# sigma_delta_v1_0.net
KiCad netlist of a schematic drawn in EAGLE
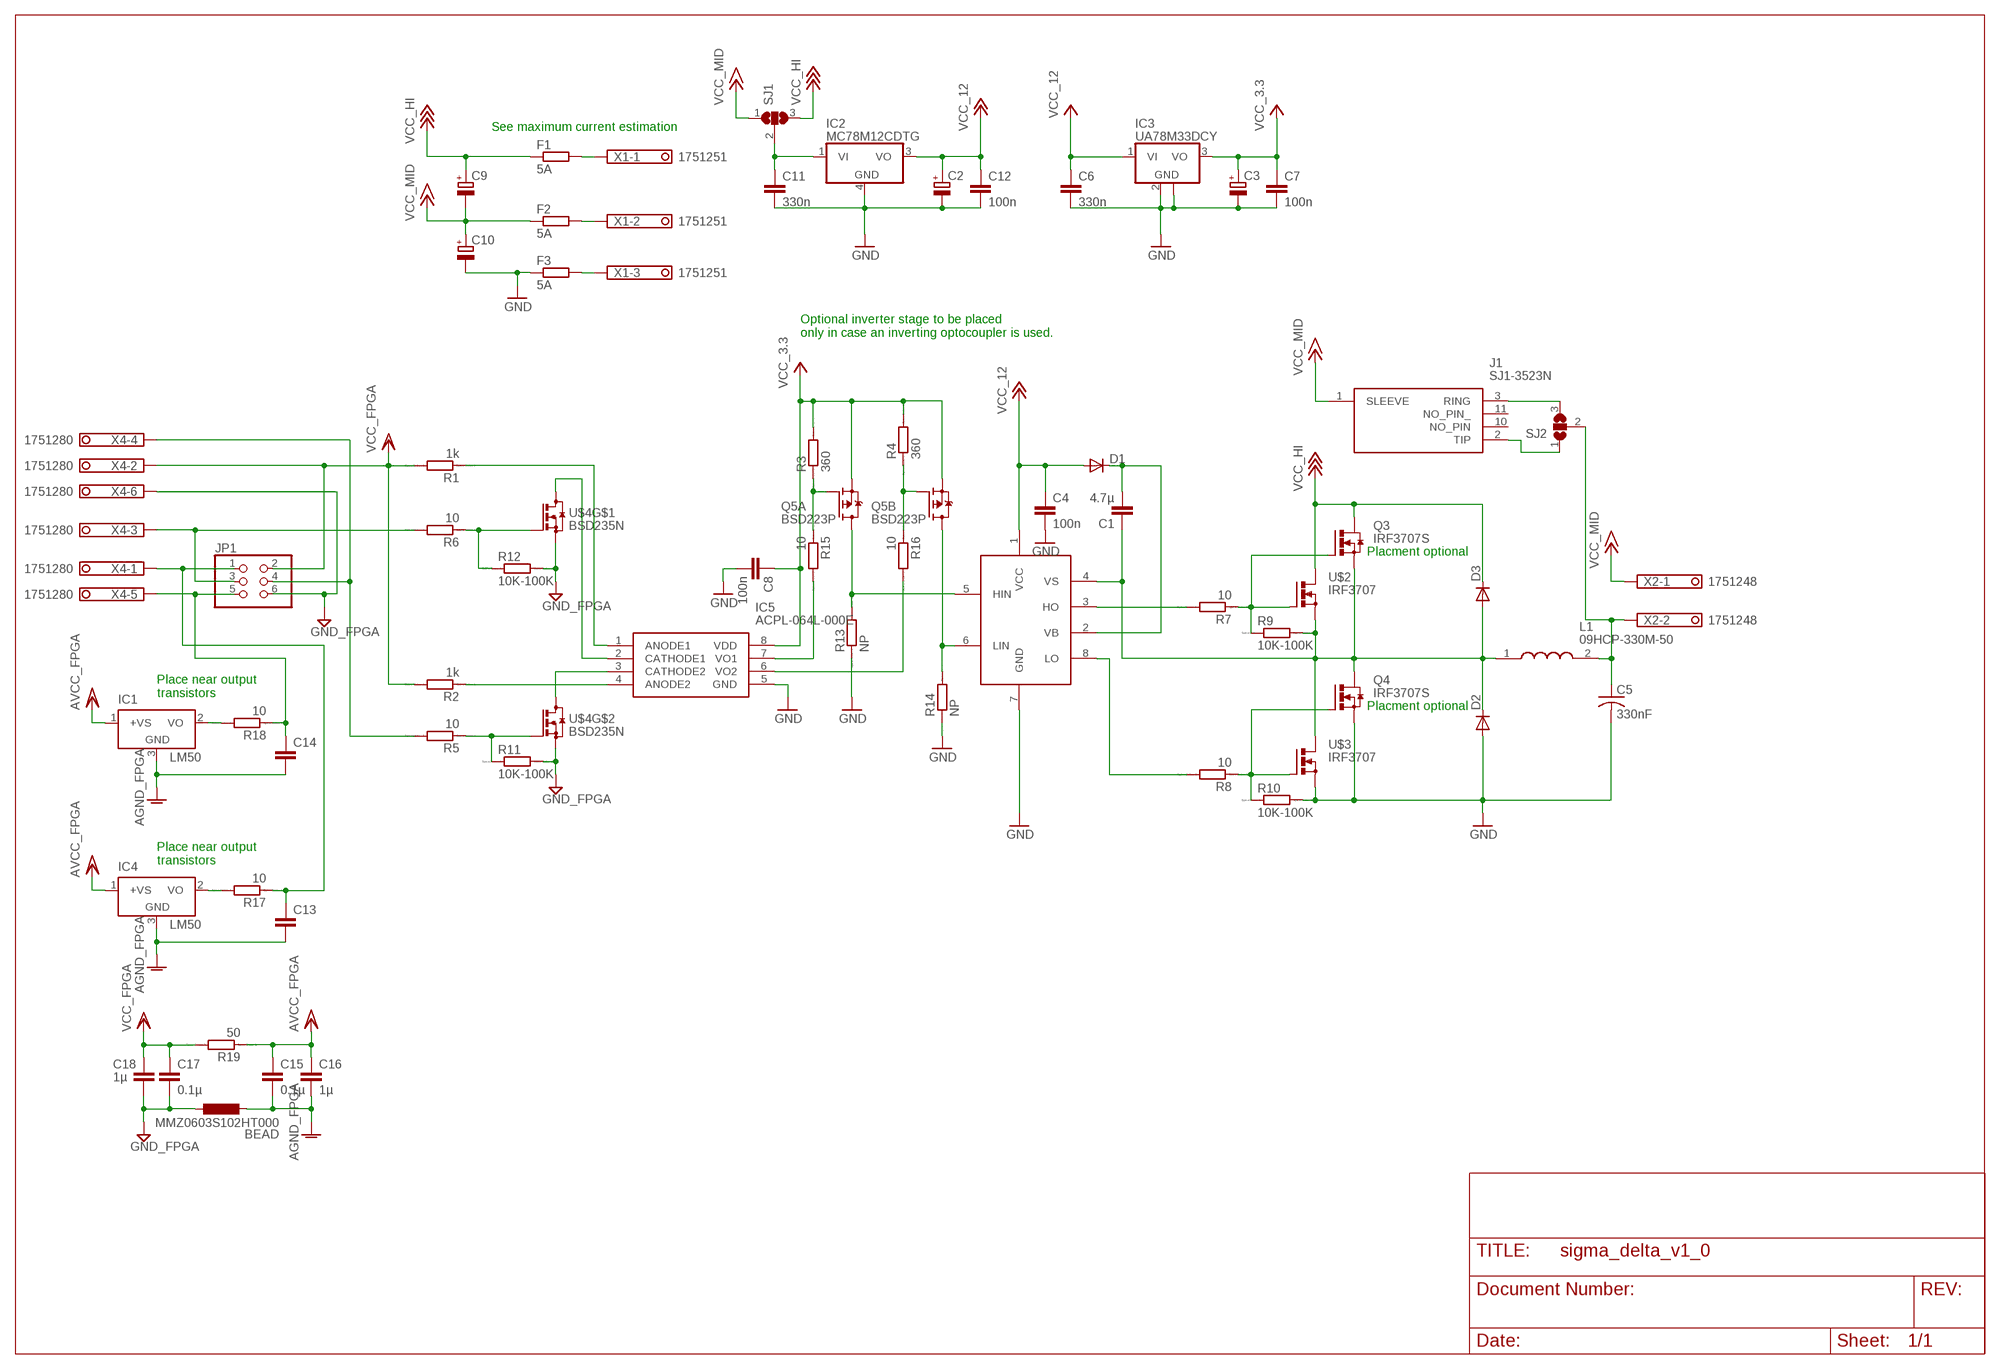
[diagram p0: schematic, sheet 1]

(export (version "E")
  (design (tool "Eeschema 10.0.6"))
  (components
    (comp (ref "BEAD")
      (value "MMZ0603S102HT000")
      (footprint "eagle-import:L2012C")
      (libsource (lib "eagle-import") (part "L-EUL2012C"))
    )
    (comp (ref "C1")
      (value "4.7µ")
      (footprint "eagle-import:C0805K")
      (libsource (lib "eagle-import") (part "C-EUC0805K"))
    )
    (comp (ref "C2")
      (value "CPOL-EUUD-6,3X7,7")
      (footprint "eagle-import:UD-6,3X7,7_NICHICON")
      (libsource (lib "eagle-import") (part "CPOL-EUUD-6,3X7,7"))
    )
    (comp (ref "C3")
      (value "CPOL-EUUD-6,3X7,7")
      (footprint "eagle-import:UD-6,3X7,7_NICHICON")
      (libsource (lib "eagle-import") (part "CPOL-EUUD-6,3X7,7"))
    )
    (comp (ref "C4")
      (value "100n")
      (footprint "eagle-import:C0805")
      (libsource (lib "eagle-import") (part "C-EUC0805"))
    )
    (comp (ref "C5")
      (value "330nF")
      (footprint "eagle-import:C2220K")
      (libsource (lib "eagle-import") (part "C-USC2220K"))
    )
    (comp (ref "C6")
      (value "330n")
      (footprint "eagle-import:C0603")
      (libsource (lib "eagle-import") (part "C-EUC0603"))
    )
    (comp (ref "C7")
      (value "100n")
      (footprint "eagle-import:C0603")
      (libsource (lib "eagle-import") (part "C-EUC0603"))
    )
    (comp (ref "C8")
      (value "100n")
      (footprint "eagle-import:C0603")
      (libsource (lib "eagle-import") (part "C-EUC0603"))
    )
    (comp (ref "C9")
      (value "CPOL-EUUD-10X10")
      (footprint "eagle-import:UD-10X10_NICHICON")
      (libsource (lib "eagle-import") (part "CPOL-EUUD-10X10"))
    )
    (comp (ref "C10")
      (value "CPOL-EUUD-10X10")
      (footprint "eagle-import:UD-10X10_NICHICON")
      (libsource (lib "eagle-import") (part "CPOL-EUUD-10X10"))
    )
    (comp (ref "C11")
      (value "330n")
      (footprint "eagle-import:C0603")
      (libsource (lib "eagle-import") (part "C-EUC0603"))
    )
    (comp (ref "C12")
      (value "100n")
      (footprint "eagle-import:C0603")
      (libsource (lib "eagle-import") (part "C-EUC0603"))
    )
    (comp (ref "C13")
      (value "C-EUC0603")
      (footprint "eagle-import:C0603")
      (libsource (lib "eagle-import") (part "C-EUC0603"))
    )
    (comp (ref "C14")
      (value "C-EUC0603")
      (footprint "eagle-import:C0603")
      (libsource (lib "eagle-import") (part "C-EUC0603"))
    )
    (comp (ref "C15")
      (value "0.1µ")
      (footprint "eagle-import:C0603")
      (libsource (lib "eagle-import") (part "C-EUC0603"))
    )
    (comp (ref "C16")
      (value "1µ")
      (footprint "eagle-import:C0603")
      (libsource (lib "eagle-import") (part "C-EUC0603"))
    )
    (comp (ref "C17")
      (value "0.1µ")
      (footprint "eagle-import:C0603")
      (libsource (lib "eagle-import") (part "C-EUC0603"))
    )
    (comp (ref "C18")
      (value "1µ")
      (footprint "eagle-import:C0603")
      (libsource (lib "eagle-import") (part "C-EUC0603"))
    )
    (comp (ref "D1")
      (value "DIODE-DO214AC")
      (footprint "eagle-import:DO214AC")
      (libsource (lib "eagle-import") (part "DIODE-DO214AC"))
    )
    (comp (ref "D2")
      (value "DIODE-DO214AC")
      (footprint "eagle-import:DO214AC")
      (libsource (lib "eagle-import") (part "DIODE-DO214AC"))
    )
    (comp (ref "D3")
      (value "DIODE-DO214AC")
      (footprint "eagle-import:DO214AC")
      (libsource (lib "eagle-import") (part "DIODE-DO214AC"))
    )
    (comp (ref "F1")
      (value "5A")
      (footprint "eagle-import:M1206")
      (libsource (lib "eagle-import") (part "R-EU_M1206"))
    )
    (comp (ref "F2")
      (value "5A")
      (footprint "eagle-import:M1206")
      (libsource (lib "eagle-import") (part "R-EU_M1206"))
    )
    (comp (ref "F3")
      (value "5A")
      (footprint "eagle-import:M1206")
      (libsource (lib "eagle-import") (part "R-EU_M1206"))
    )
    (comp (ref "IC1")
      (value "LM50")
      (footprint "eagle-import:SOT23")
      (libsource (lib "eagle-import") (part "LM50"))
    )
    (comp (ref "IC2")
      (value "MC78M12CDTG")
      (footprint "eagle-import:DPACK_3")
      (libsource (lib "eagle-import") (part "MC78M12CDTG"))
    )
    (comp (ref "IC3")
      (value "UA78M33DCY")
      (footprint "eagle-import:SOT223")
      (libsource (lib "eagle-import") (part "UA78MDCY33"))
    )
    (comp (ref "IC4")
      (value "LM50")
      (footprint "eagle-import:SOT23")
      (libsource (lib "eagle-import") (part "LM50"))
    )
    (comp (ref "IC5")
      (value "ACPL-064L-000E")
      (footprint "eagle-import:SOIC127P599X330-8N")
      (fields (field (name "MOUSER_PART_NUMBER") "630-ACPL-064L-000E"))
      (libsource (lib "eagle-import") (part "ACPL-064L-000E"))
    )
    (comp (ref "J1")
      (value "SJ1-3523N")
      (footprint "eagle-import:SJ13523N")
      (fields (field (name "MOUSER_PART_NUMBER") "490-SJ1-3523N"))
      (libsource (lib "eagle-import") (part "SJ1-3523N"))
    )
    (comp (ref "JP1")
      (value "PINHD-2X3_2.54")
      (footprint "eagle-import:2X03")
      (libsource (lib "eagle-import") (part "PINHD-2X3_2.54"))
    )
    (comp (ref "L1")
      (value "09HCP-330M-50")
      (footprint "eagle-import:09HCP330M50")
      (fields (field (name "MOUSER_PART_NUMBER") "434-09HCP-330M"))
      (libsource (lib "eagle-import") (part "09HCP-330M-50"))
    )
    (comp (ref "Q3")
      (value "IRF3707S")
      (footprint "eagle-import:D2PACK")
      (libsource (lib "eagle-import") (part "IRF3704S"))
    )
    (comp (ref "Q4")
      (value "IRF3707S")
      (footprint "eagle-import:D2PACK")
      (libsource (lib "eagle-import") (part "IRF3704S"))
    )
    (comp (ref "Q5")
      (value "BSD223P")
      (footprint "eagle-import:SOT363_INFINEON")
      (libsource (lib "eagle-import") (part "BSD223P"))
    )
    (comp (ref "R1")
      (value "1k")
      (footprint "eagle-import:R0603")
      (libsource (lib "eagle-import") (part "RR0603"))
    )
    (comp (ref "R2")
      (value "1k")
      (footprint "eagle-import:R0603")
      (libsource (lib "eagle-import") (part "RR0603"))
    )
    (comp (ref "R3")
      (value "360")
      (footprint "eagle-import:R0603")
      (libsource (lib "eagle-import") (part "RR0603"))
    )
    (comp (ref "R4")
      (value "360")
      (footprint "eagle-import:R0603")
      (libsource (lib "eagle-import") (part "RR0603"))
    )
    (comp (ref "R5")
      (value "10")
      (footprint "eagle-import:R0603")
      (libsource (lib "eagle-import") (part "RR0603"))
    )
    (comp (ref "R6")
      (value "10")
      (footprint "eagle-import:R0603")
      (libsource (lib "eagle-import") (part "RR0603"))
    )
    (comp (ref "R7")
      (value "10")
      (footprint "eagle-import:R0603")
      (libsource (lib "eagle-import") (part "RR0603"))
    )
    (comp (ref "R8")
      (value "10")
      (footprint "eagle-import:R0603")
      (libsource (lib "eagle-import") (part "RR0603"))
    )
    (comp (ref "R9")
      (value "10K-100K")
      (footprint "eagle-import:R0603")
      (libsource (lib "eagle-import") (part "RR0603"))
    )
    (comp (ref "R10")
      (value "10K-100K")
      (footprint "eagle-import:R0603")
      (libsource (lib "eagle-import") (part "RR0603"))
    )
    (comp (ref "R11")
      (value "10K-100K")
      (footprint "eagle-import:R0603")
      (libsource (lib "eagle-import") (part "RR0603"))
    )
    (comp (ref "R12")
      (value "10K-100K")
      (footprint "eagle-import:R0603")
      (libsource (lib "eagle-import") (part "RR0603"))
    )
    (comp (ref "R13")
      (value "NP")
      (footprint "eagle-import:R0603")
      (libsource (lib "eagle-import") (part "RR0603"))
    )
    (comp (ref "R14")
      (value "NP")
      (footprint "eagle-import:R0603")
      (libsource (lib "eagle-import") (part "RR0603"))
    )
    (comp (ref "R15")
      (value "10")
      (footprint "eagle-import:R0603")
      (libsource (lib "eagle-import") (part "RR0603"))
    )
    (comp (ref "R16")
      (value "10")
      (footprint "eagle-import:R0603")
      (libsource (lib "eagle-import") (part "RR0603"))
    )
    (comp (ref "R17")
      (value "10")
      (footprint "eagle-import:R0603")
      (libsource (lib "eagle-import") (part "RR0603"))
    )
    (comp (ref "R18")
      (value "10")
      (footprint "eagle-import:R0603")
      (libsource (lib "eagle-import") (part "RR0603"))
    )
    (comp (ref "R19")
      (value "50")
      (footprint "eagle-import:R0603")
      (libsource (lib "eagle-import") (part "RR0603"))
    )
    (comp (ref "SJ1")
      (value "SJ2W")
      (footprint "eagle-import:SJ_2")
      (libsource (lib "eagle-import") (part "SJ2W"))
    )
    (comp (ref "SJ2")
      (value "SJ2WW")
      (footprint "eagle-import:SJ_2W")
      (libsource (lib "eagle-import") (part "SJ2WW"))
    )
    (comp (ref "U$1")
      (value "IR2011")
      (footprint "eagle-import:SO08")
      (libsource (lib "eagle-import") (part "IR2011"))
    )
    (comp (ref "U$2")
      (value "IRF3707")
      (footprint "eagle-import:TO220BV")
      (libsource (lib "eagle-import") (part "BUZ11BV"))
    )
    (comp (ref "U$3")
      (value "IRF3707")
      (footprint "eagle-import:TO220BV")
      (libsource (lib "eagle-import") (part "BUZ11BV"))
    )
    (comp (ref "U$4")
      (value "BSD235N")
      (footprint "eagle-import:SOT65P210X100-6N")
      (libsource (lib "eagle-import") (part "BSD235N"))
    )
    (comp (ref "X1")
      (value "1751251")
      (footprint "eagle-import:1751251")
      (libsource (lib "eagle-import") (part "1751251"))
    )
    (comp (ref "X2")
      (value "1751248")
      (footprint "eagle-import:1751248")
      (libsource (lib "eagle-import") (part "1751248"))
    )
    (comp (ref "X4")
      (value "1751280")
      (footprint "eagle-import:1751280")
      (libsource (lib "eagle-import") (part "1751280"))
    )
  )
  (nets
    (net (code "1") (name "AGND_FPGA") (class "Default")
      (node (ref "BEAD") (pin "2") (pinfunction "2_2") (pintype "passive"))
      (node (ref "C13") (pin "2") (pinfunction "2_2") (pintype "passive"))
      (node (ref "C14") (pin "2") (pinfunction "2_2") (pintype "passive"))
      (node (ref "C15") (pin "2") (pinfunction "2_2") (pintype "passive"))
      (node (ref "C16") (pin "2") (pinfunction "2_2") (pintype "passive"))
      (node (ref "IC1") (pin "3") (pinfunction "GND_3") (pintype "power_in"))
      (node (ref "IC4") (pin "3") (pinfunction "GND_3") (pintype "power_in"))
    )
    (net (code "2") (name "AVCC_FPGA") (class "Default")
      (node (ref "C15") (pin "1") (pinfunction "1_1") (pintype "passive"))
      (node (ref "C16") (pin "1") (pinfunction "1_1") (pintype "passive"))
      (node (ref "IC1") (pin "1") (pinfunction "+VS_1") (pintype "input"))
      (node (ref "IC4") (pin "1") (pinfunction "+VS_1") (pintype "input"))
      (node (ref "R19") (pin "1") (pinfunction "1_1") (pintype "passive"))
    )
    (net (code "3") (name "GND") (class "Default")
      (node (ref "C10") (pin "-") (pinfunction "-_-") (pintype "passive"))
      (node (ref "C11") (pin "2") (pinfunction "2_2") (pintype "passive"))
      (node (ref "C12") (pin "2") (pinfunction "2_2") (pintype "passive"))
      (node (ref "C2") (pin "-") (pinfunction "-_-") (pintype "passive"))
      (node (ref "C3") (pin "-") (pinfunction "-_-") (pintype "passive"))
      (node (ref "C4") (pin "2") (pinfunction "2_2") (pintype "passive"))
      (node (ref "C5") (pin "2") (pinfunction "2_2") (pintype "passive"))
      (node (ref "C6") (pin "2") (pinfunction "2_2") (pintype "passive"))
      (node (ref "C7") (pin "2") (pinfunction "2_2") (pintype "passive"))
      (node (ref "C8") (pin "2") (pinfunction "2_2") (pintype "passive"))
      (node (ref "D2") (pin "A") (pinfunction "A_A") (pintype "passive"))
      (node (ref "F3") (pin "1") (pinfunction "1_1") (pintype "passive"))
      (node (ref "IC2") (pin "4") (pinfunction "GND_4") (pintype "passive"))
      (node (ref "IC3") (pin "2") (pinfunction "GND_2") (pintype "passive"))
      (node (ref "IC3") (pin "4") (pinfunction "GND_4") (pintype "passive"))
      (node (ref "IC5") (pin "5") (pinfunction "GND_5") (pintype "bidirectional"))
      (node (ref "Q4") (pin "3") (pinfunction "S_3") (pintype "passive"))
      (node (ref "R10") (pin "2") (pinfunction "2_2") (pintype "passive"))
      (node (ref "R13") (pin "1") (pinfunction "1_1") (pintype "passive"))
      (node (ref "R14") (pin "1") (pinfunction "1_1") (pintype "passive"))
      (node (ref "U$1") (pin "7") (pinfunction "GND_7") (pintype "power_in"))
      (node (ref "U$3") (pin "S") (pinfunction "S_S") (pintype "passive"))
    )
    (net (code "4") (name "GND_FPGA") (class "Default")
      (node (ref "BEAD") (pin "1") (pinfunction "1_1") (pintype "passive"))
      (node (ref "C17") (pin "2") (pinfunction "2_2") (pintype "passive"))
      (node (ref "C18") (pin "2") (pinfunction "2_2") (pintype "passive"))
      (node (ref "JP1") (pin "6") (pinfunction "6_6") (pintype "passive"))
      (node (ref "R11") (pin "2") (pinfunction "2_2") (pintype "passive"))
      (node (ref "R12") (pin "2") (pinfunction "2_2") (pintype "passive"))
      (node (ref "U$4") (pin "1") (pinfunction "S_1") (pintype "passive"))
      (node (ref "U$4") (pin "4") (pinfunction "S_4") (pintype "passive"))
      (node (ref "X4") (pin "6") (pinfunction "K_6") (pintype "passive"))
    )
    (net (code "5") (name "Net-(IC1-VO)") (class "Default")
      (node (ref "IC1") (pin "2") (pinfunction "VO_2") (pintype "input"))
      (node (ref "R18") (pin "2") (pinfunction "2_2") (pintype "passive"))
    )
    (net (code "6") (name "Net-(IC2-VI)") (class "Default")
      (node (ref "C11") (pin "1") (pinfunction "1_1") (pintype "passive"))
      (node (ref "IC2") (pin "1") (pinfunction "VI_1") (pintype "input"))
      (node (ref "SJ1") (pin "2") (pinfunction "2_2") (pintype "passive"))
    )
    (net (code "7") (name "Net-(IC4-VO)") (class "Default")
      (node (ref "IC4") (pin "2") (pinfunction "VO_2") (pintype "input"))
      (node (ref "R17") (pin "2") (pinfunction "2_2") (pintype "passive"))
    )
    (net (code "8") (name "Net-(IC5-ANODE1)") (class "Default")
      (node (ref "IC5") (pin "1") (pinfunction "ANODE1_1") (pintype "bidirectional"))
      (node (ref "R1") (pin "1") (pinfunction "1_1") (pintype "passive"))
    )
    (net (code "9") (name "Net-(IC5-ANODE2)") (class "Default")
      (node (ref "IC5") (pin "4") (pinfunction "ANODE2_4") (pintype "bidirectional"))
      (node (ref "R2") (pin "1") (pinfunction "1_1") (pintype "passive"))
    )
    (net (code "10") (name "Net-(IC5-CATHODE1)") (class "Default")
      (node (ref "IC5") (pin "2") (pinfunction "CATHODE1_2") (pintype "bidirectional"))
      (node (ref "U$4") (pin "6") (pinfunction "D_6") (pintype "passive"))
    )
    (net (code "11") (name "Net-(IC5-CATHODE2)") (class "Default")
      (node (ref "IC5") (pin "3") (pinfunction "CATHODE2_3") (pintype "bidirectional"))
      (node (ref "U$4") (pin "3") (pinfunction "D_3") (pintype "passive"))
    )
    (net (code "12") (name "Net-(IC5-VO1)") (class "Default")
      (node (ref "IC5") (pin "7") (pinfunction "VO1_7") (pintype "bidirectional"))
      (node (ref "R15") (pin "2") (pinfunction "2_2") (pintype "passive"))
    )
    (net (code "13") (name "Net-(IC5-VO2)") (class "Default")
      (node (ref "IC5") (pin "6") (pinfunction "VO2_6") (pintype "bidirectional"))
      (node (ref "R16") (pin "2") (pinfunction "2_2") (pintype "passive"))
    )
    (net (code "14") (name "Net-(J1-RING)") (class "Default")
      (node (ref "J1") (pin "3") (pinfunction "RING_3") (pintype "bidirectional"))
      (node (ref "SJ2") (pin "3") (pinfunction "3_3") (pintype "passive"))
    )
    (net (code "15") (name "Net-(J1-TIP)") (class "Default")
      (node (ref "J1") (pin "2") (pinfunction "TIP_2") (pintype "bidirectional"))
      (node (ref "SJ2") (pin "1") (pinfunction "1_1") (pintype "passive"))
    )
    (net (code "16") (name "Net-(Q3-G)") (class "Default")
      (node (ref "Q3") (pin "1") (pinfunction "G_1") (pintype "passive"))
      (node (ref "R7") (pin "1") (pinfunction "1_1") (pintype "passive"))
      (node (ref "R9") (pin "1") (pinfunction "1_1") (pintype "passive"))
      (node (ref "U$2") (pin "G") (pinfunction "G_G") (pintype "passive"))
    )
    (net (code "17") (name "Net-(Q3-S)") (class "Default")
      (node (ref "C1") (pin "1") (pinfunction "1_1") (pintype "passive"))
      (node (ref "D2") (pin "C") (pinfunction "C_C") (pintype "passive"))
      (node (ref "D3") (pin "A") (pinfunction "A_A") (pintype "passive"))
      (node (ref "L1") (pin "1") (pinfunction "1_1") (pintype "bidirectional"))
      (node (ref "Q3") (pin "3") (pinfunction "S_3") (pintype "passive"))
      (node (ref "Q4") (pin "2") (pinfunction "D_2") (pintype "passive"))
      (node (ref "R9") (pin "2") (pinfunction "2_2") (pintype "passive"))
      (node (ref "U$1") (pin "4") (pinfunction "VS_4") (pintype "bidirectional"))
      (node (ref "U$2") (pin "S") (pinfunction "S_S") (pintype "passive"))
      (node (ref "U$3") (pin "D") (pinfunction "D_D") (pintype "passive"))
    )
    (net (code "18") (name "Net-(Q4-G)") (class "Default")
      (node (ref "Q4") (pin "1") (pinfunction "G_1") (pintype "passive"))
      (node (ref "R10") (pin "1") (pinfunction "1_1") (pintype "passive"))
      (node (ref "R8") (pin "1") (pinfunction "1_1") (pintype "passive"))
      (node (ref "U$3") (pin "G") (pinfunction "G_G") (pintype "passive"))
    )
    (net (code "19") (name "Net-(Q5A-D)") (class "Default")
      (node (ref "Q5") (pin "6") (pinfunction "D_6") (pintype "passive"))
      (node (ref "R13") (pin "2") (pinfunction "2_2") (pintype "passive"))
      (node (ref "U$1") (pin "5") (pinfunction "HIN_5") (pintype "input"))
    )
    (net (code "20") (name "Net-(Q5A-G)") (class "Default")
      (node (ref "Q5") (pin "2") (pinfunction "G_2") (pintype "passive"))
      (node (ref "R15") (pin "1") (pinfunction "1_1") (pintype "passive"))
      (node (ref "R3") (pin "1") (pinfunction "1_1") (pintype "passive"))
    )
    (net (code "21") (name "Net-(Q5B-D)") (class "Default")
      (node (ref "Q5") (pin "3") (pinfunction "D_3") (pintype "passive"))
      (node (ref "R14") (pin "2") (pinfunction "2_2") (pintype "passive"))
      (node (ref "U$1") (pin "6") (pinfunction "LIN_6") (pintype "input"))
    )
    (net (code "22") (name "Net-(Q5B-G)") (class "Default")
      (node (ref "Q5") (pin "5") (pinfunction "G_5") (pintype "passive"))
      (node (ref "R16") (pin "1") (pinfunction "1_1") (pintype "passive"))
      (node (ref "R4") (pin "1") (pinfunction "1_1") (pintype "passive"))
    )
    (net (code "23") (name "Net-(U$1-HO)") (class "Default")
      (node (ref "R7") (pin "2") (pinfunction "2_2") (pintype "passive"))
      (node (ref "U$1") (pin "3") (pinfunction "HO_3") (pintype "output"))
    )
    (net (code "24") (name "Net-(U$1-LO)") (class "Default")
      (node (ref "R8") (pin "2") (pinfunction "2_2") (pintype "passive"))
      (node (ref "U$1") (pin "8") (pinfunction "LO_8") (pintype "output"))
    )
    (net (code "25") (name "Net-(U$1-VB)") (class "Default")
      (node (ref "C1") (pin "2") (pinfunction "2_2") (pintype "passive"))
      (node (ref "D1") (pin "C") (pinfunction "C_C") (pintype "passive"))
      (node (ref "U$1") (pin "2") (pinfunction "VB_2") (pintype "bidirectional"))
    )
    (net (code "26") (name "Net-(U$4A-G)") (class "Default")
      (node (ref "R12") (pin "1") (pinfunction "1_1") (pintype "passive"))
      (node (ref "R6") (pin "1") (pinfunction "1_1") (pintype "passive"))
      (node (ref "U$4") (pin "2") (pinfunction "G_2") (pintype "passive"))
    )
    (net (code "27") (name "Net-(U$4B-G)") (class "Default")
      (node (ref "R11") (pin "1") (pinfunction "1_1") (pintype "passive"))
      (node (ref "R5") (pin "1") (pinfunction "1_1") (pintype "passive"))
      (node (ref "U$4") (pin "5") (pinfunction "G_5") (pintype "passive"))
    )
    (net (code "28") (name "Net-(X1A-K)") (class "Default")
      (node (ref "F1") (pin "2") (pinfunction "2_2") (pintype "passive"))
      (node (ref "X1") (pin "1") (pinfunction "K_1") (pintype "passive"))
    )
    (net (code "29") (name "Net-(X1B-K)") (class "Default")
      (node (ref "F2") (pin "2") (pinfunction "2_2") (pintype "passive"))
      (node (ref "X1") (pin "2") (pinfunction "K_2") (pintype "passive"))
    )
    (net (code "30") (name "Net-(X1C-K)") (class "Default")
      (node (ref "F3") (pin "2") (pinfunction "2_2") (pintype "passive"))
      (node (ref "X1") (pin "3") (pinfunction "K_3") (pintype "passive"))
    )
    (net (code "31") (name "Net-(X2B-K)") (class "Default")
      (node (ref "C5") (pin "1") (pinfunction "1_1") (pintype "passive"))
      (node (ref "L1") (pin "2") (pinfunction "2_2") (pintype "bidirectional"))
      (node (ref "SJ2") (pin "2") (pinfunction "2_2") (pintype "passive"))
      (node (ref "X2") (pin "2") (pinfunction "K_2") (pintype "passive"))
    )
    (net (code "32") (name "Net-(X4A-K)") (class "Default")
      (node (ref "C13") (pin "1") (pinfunction "1_1") (pintype "passive"))
      (node (ref "JP1") (pin "1") (pinfunction "1_1") (pintype "passive"))
      (node (ref "R17") (pin "1") (pinfunction "1_1") (pintype "passive"))
      (node (ref "X4") (pin "1") (pinfunction "K_1") (pintype "passive"))
    )
    (net (code "33") (name "Net-(X4C-K)") (class "Default")
      (node (ref "JP1") (pin "3") (pinfunction "3_3") (pintype "passive"))
      (node (ref "R6") (pin "2") (pinfunction "2_2") (pintype "passive"))
      (node (ref "X4") (pin "3") (pinfunction "K_3") (pintype "passive"))
    )
    (net (code "34") (name "Net-(X4D-K)") (class "Default")
      (node (ref "JP1") (pin "4") (pinfunction "4_4") (pintype "passive"))
      (node (ref "R5") (pin "2") (pinfunction "2_2") (pintype "passive"))
      (node (ref "X4") (pin "4") (pinfunction "K_4") (pintype "passive"))
    )
    (net (code "35") (name "Net-(X4E-K)") (class "Default")
      (node (ref "C14") (pin "1") (pinfunction "1_1") (pintype "passive"))
      (node (ref "JP1") (pin "5") (pinfunction "5_5") (pintype "passive"))
      (node (ref "R18") (pin "1") (pinfunction "1_1") (pintype "passive"))
      (node (ref "X4") (pin "5") (pinfunction "K_5") (pintype "passive"))
    )
    (net (code "36") (name "VCC_3.3") (class "Default")
      (node (ref "C3") (pin "+") (pinfunction "+_+") (pintype "passive"))
      (node (ref "C7") (pin "1") (pinfunction "1_1") (pintype "passive"))
      (node (ref "C8") (pin "1") (pinfunction "1_1") (pintype "passive"))
      (node (ref "IC3") (pin "3") (pinfunction "VO_3") (pintype "passive"))
      (node (ref "IC5") (pin "8") (pinfunction "VDD_8") (pintype "bidirectional"))
      (node (ref "Q5") (pin "1") (pinfunction "S_1") (pintype "passive"))
      (node (ref "Q5") (pin "4") (pinfunction "S_4") (pintype "passive"))
      (node (ref "R3") (pin "2") (pinfunction "2_2") (pintype "passive"))
      (node (ref "R4") (pin "2") (pinfunction "2_2") (pintype "passive"))
    )
    (net (code "37") (name "VCC_12") (class "Default")
      (node (ref "C12") (pin "1") (pinfunction "1_1") (pintype "passive"))
      (node (ref "C2") (pin "+") (pinfunction "+_+") (pintype "passive"))
      (node (ref "C4") (pin "1") (pinfunction "1_1") (pintype "passive"))
      (node (ref "C6") (pin "1") (pinfunction "1_1") (pintype "passive"))
      (node (ref "D1") (pin "A") (pinfunction "A_A") (pintype "passive"))
      (node (ref "IC2") (pin "3") (pinfunction "VO_3") (pintype "passive"))
      (node (ref "IC3") (pin "1") (pinfunction "VI_1") (pintype "input"))
      (node (ref "U$1") (pin "1") (pinfunction "VCC_1") (pintype "power_in"))
    )
    (net (code "38") (name "VCC_FPGA") (class "Default")
      (node (ref "C17") (pin "1") (pinfunction "1_1") (pintype "passive"))
      (node (ref "C18") (pin "1") (pinfunction "1_1") (pintype "passive"))
      (node (ref "JP1") (pin "2") (pinfunction "2_2") (pintype "passive"))
      (node (ref "R1") (pin "2") (pinfunction "2_2") (pintype "passive"))
      (node (ref "R19") (pin "2") (pinfunction "2_2") (pintype "passive"))
      (node (ref "R2") (pin "2") (pinfunction "2_2") (pintype "passive"))
      (node (ref "X4") (pin "2") (pinfunction "K_2") (pintype "passive"))
    )
    (net (code "39") (name "VCC_HI") (class "Default")
      (node (ref "C9") (pin "+") (pinfunction "+_+") (pintype "passive"))
      (node (ref "D3") (pin "C") (pinfunction "C_C") (pintype "passive"))
      (node (ref "F1") (pin "1") (pinfunction "1_1") (pintype "passive"))
      (node (ref "Q3") (pin "2") (pinfunction "D_2") (pintype "passive"))
      (node (ref "SJ1") (pin "3") (pinfunction "3_3") (pintype "passive"))
      (node (ref "U$2") (pin "D") (pinfunction "D_D") (pintype "passive"))
    )
    (net (code "40") (name "VCC_MID") (class "Default")
      (node (ref "C10") (pin "+") (pinfunction "+_+") (pintype "passive"))
      (node (ref "C9") (pin "-") (pinfunction "-_-") (pintype "passive"))
      (node (ref "F2") (pin "1") (pinfunction "1_1") (pintype "passive"))
      (node (ref "J1") (pin "1") (pinfunction "SLEEVE_1") (pintype "bidirectional"))
      (node (ref "SJ1") (pin "1") (pinfunction "1_1") (pintype "passive"))
      (node (ref "X2") (pin "1") (pinfunction "K_1") (pintype "passive"))
    )
    (net (code "41") (name "unconnected-(J1-NO_PIN-Pad10)") (class "Default")
      (node (ref "J1") (pin "10") (pinfunction "NO_PIN_10") (pintype "bidirectional"))
    )
    (net (code "42") (name "unconnected-(J1-NO_PIN_-Pad11)") (class "Default")
      (node (ref "J1") (pin "11") (pinfunction "NO_PIN__11") (pintype "bidirectional"))
    )
  )
)
